# 1_PFC.net
KiCad netlist of a schematic drawn in Altium Designer
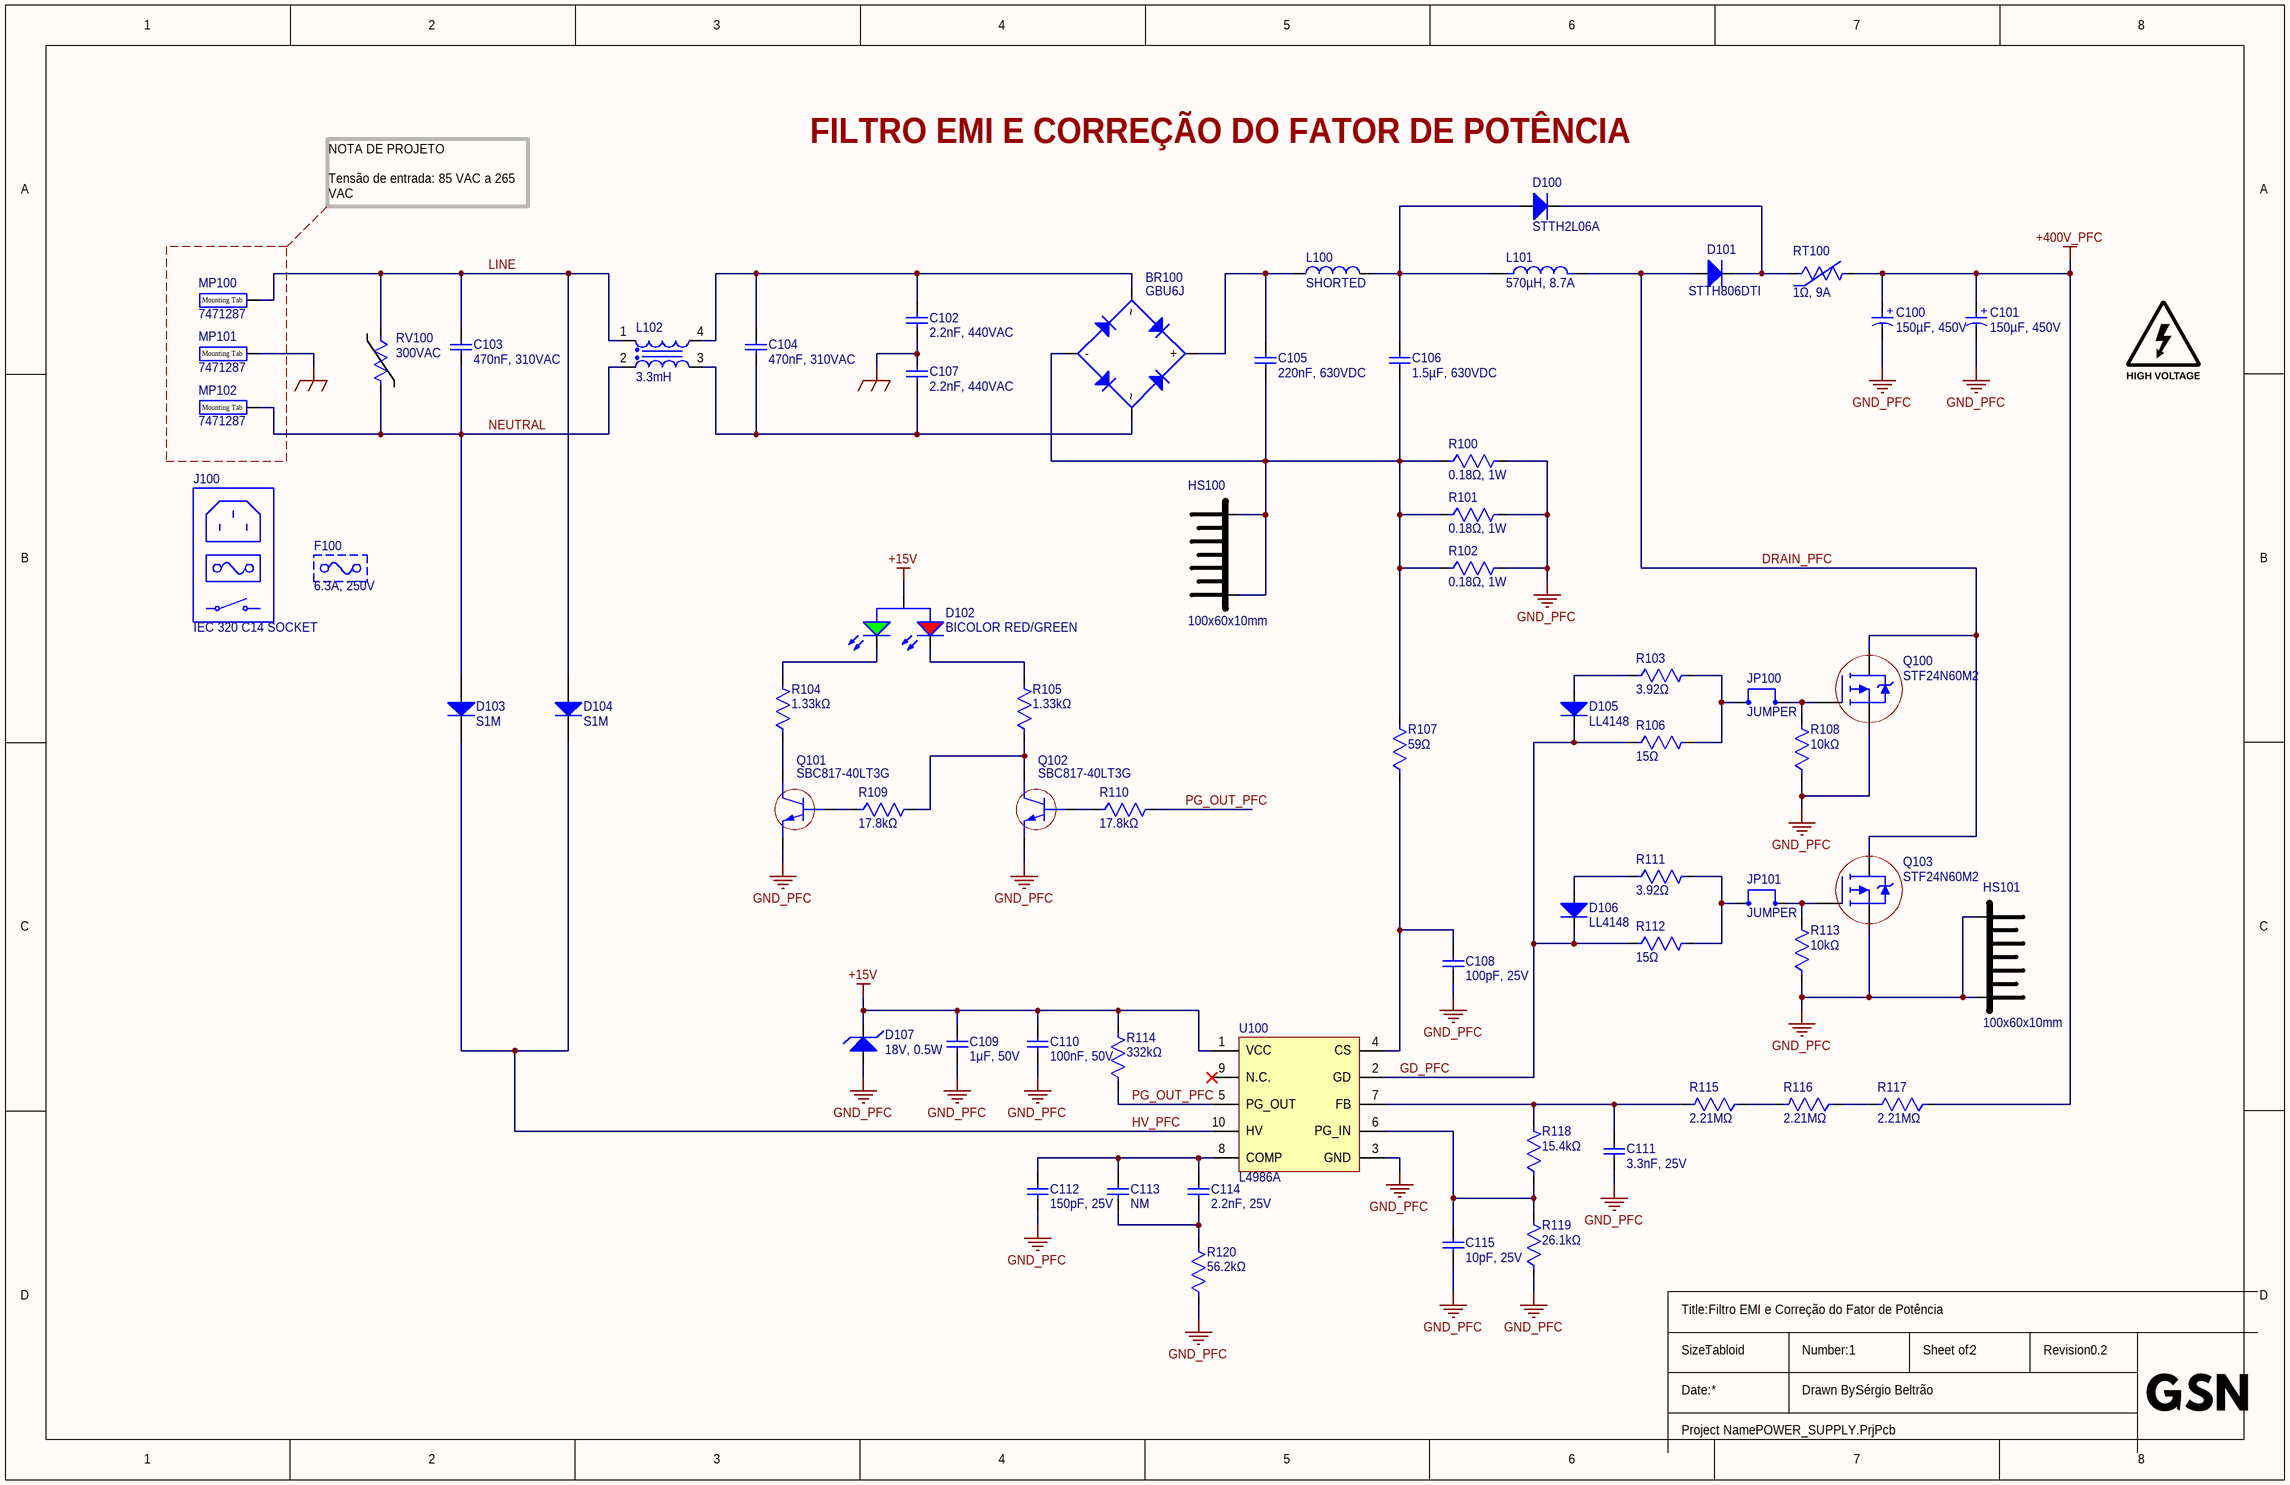
[diagram p0: 1_PFC.SchDoc]

(export (version "E")
  (design (tool "Eeschema 10.0.6"))
  (components
    (comp (ref "BR100")
      (value "GBU6J")
      (footprint "GBU")
      (description "BRIDGE RECT 1PHASE 600V 6A GBU")
      (fields (field (name "MANUFACTURER") "onsemi"))
      (libsource (lib "Bridge-Rectifiers") (part "GBU6J"))
    )
    (comp (ref "C100")
      (value "150µF, 450V")
      (footprint "WCAP-AIG8_D22H50")
      (description "WCAP-AIG8 Aluminum Electrolytic Capacitor, Snap-In, D22 x H50mm, 150µF, 450V")
      (fields
        (field (name "MANUFACTURER PART NUMBER") "861011483006")
        (field (name "MANUFACTURER") "Wurth Elektronik")
      )
      (libsource (lib "WE - Passive Components") (part "Capacitor_Polarized"))
    )
    (comp (ref "C101")
      (value "150µF, 450V")
      (footprint "WCAP-AIG8_D22H50")
      (description "WCAP-AIG8 Aluminum Electrolytic Capacitor, Snap-In, D22 x H50mm, 150µF, 450V")
      (fields
        (field (name "MANUFACTURER PART NUMBER") "861011483006")
        (field (name "MANUFACTURER") "Wurth Elektronik")
      )
      (libsource (lib "WE - Passive Components") (part "Capacitor_Polarized"))
    )
    (comp (ref "C102")
      (value "2.2nF, 440VAC")
      (footprint "CAP_5US63V7_VIS")
      (description "CAP CER 2200PF 440VAC Y5U RADIAL")
      (fields
        (field (name "MANUFACTURER") "Vishay")
        (field (name "MANUFACTURER PART NUMBER") "VY2222M35Y5US63V7")
      )
      (libsource (lib "Capacitors-PTH-Ceramic") (part "VY2222M35Y5US63V7"))
    )
    (comp (ref "C103")
      (value "470nF, 310VAC")
      (footprint "WCAP-FTXX_L18W8H14")
      (description "WCAP-FTXX Film Capacitor, THT, 18mm x 8mm x 14mm, 470nF, 310V")
      (fields
        (field (name "MANUFACTURER PART NUMBER") "890334025039CS")
        (field (name "MANUFACTURER") "Wurth Elektronik")
      )
      (libsource (lib "WE - Passive Components") (part "Capacitor_Non-Polarized"))
    )
    (comp (ref "C104")
      (value "470nF, 310VAC")
      (footprint "WCAP-FTXX_L18W8H14")
      (description "WCAP-FTXX Film Capacitor, THT, 18mm x 8mm x 14mm, 470nF, 310V")
      (fields
        (field (name "MANUFACTURER PART NUMBER") "890334025039CS")
        (field (name "MANUFACTURER") "Wurth Elektronik")
      )
      (libsource (lib "WE - Passive Components") (part "Capacitor_Non-Polarized"))
    )
    (comp (ref "C105")
      (value "220nF, 630VDC")
      (footprint "WCAP-FTXH_L18W8.5H14.5")
      (description "WCAP-FTXH THB X2-Capacitor, THT, L18 x W8.5 x H14.5mm, 220nF, 310V")
      (fields
        (field (name "MANUFACTURER PART NUMBER") "890414025003CS")
        (field (name "MANUFACTURER") "Wurth Elektronik")
      )
      (libsource (lib "WE - Passive Components") (part "Capacitor_Non-Polarized"))
    )
    (comp (ref "C106")
      (value "1.5µF, 630VDC")
      (footprint "WCAP-FTXH_L26.5W14.5H24.5")
      (description "WCAP-FTXH THB X2-Capacitor, THT, L26.5 x W14.5 x H24.5mm, 1.5µF, 310V")
      (fields
        (field (name "MANUFACTURER PART NUMBER") "890414026009CS")
        (field (name "MANUFACTURER") "Wurth Elektronik")
      )
      (libsource (lib "WE - Passive Components") (part "Capacitor_Non-Polarized"))
    )
    (comp (ref "C107")
      (value "2.2nF, 440VAC")
      (footprint "CAP_5US63V7_VIS")
      (description "CAP CER 2200PF 440VAC Y5U RADIAL")
      (fields
        (field (name "MANUFACTURER") "Vishay")
        (field (name "MANUFACTURER PART NUMBER") "VY2222M35Y5US63V7")
      )
      (libsource (lib "Capacitors-PTH-Ceramic") (part "VY2222M35Y5US63V7"))
    )
    (comp (ref "C108")
      (value "100pF, 25V")
      (footprint "WCAP-CSGP_0603_L1.6W0.8H0.8_Wave")
      (description "WCAP-CSGP Multilayer Ceramic Chip Capacitor, General Purpose, size 0603, 100pF, 25V")
      (fields
        (field (name "MANUFACTURER PART NUMBER") "885012206053")
        (field (name "MANUFACTURER") "Wurth Elektronik")
      )
      (libsource (lib "WE - Passive Components") (part "Capacitor_Non-Polarized"))
    )
    (comp (ref "C109")
      (value "1μF, 50V")
      (footprint "WCAP-CSGP_0603_L1.6W0.8H0.8_Wave")
      (description "WCAP-CSGP Multilayer Ceramic Chip Capacitor, General Purpose, size 0603, 1μF, 50V")
      (fields
        (field (name "MANUFACTURER PART NUMBER") "885012206126")
        (field (name "MANUFACTURER") "Wurth Elektronik")
      )
      (libsource (lib "WE - Passive Components") (part "Capacitor_Non-Polarized"))
    )
    (comp (ref "C110")
      (value "100nF, 50V")
      (footprint "WCAP-CSGP_0603_L1.6W0.8H0.8_Wave")
      (description "WCAP-CSGP Multilayer Ceramic Chip Capacitor, General Purpose, size 0603, 100nF, 50V")
      (fields
        (field (name "MANUFACTURER PART NUMBER") "885012206095R")
        (field (name "MANUFACTURER") "Wurth Elektronik")
      )
      (libsource (lib "WE - Passive Components") (part "Capacitor_Non-Polarized"))
    )
    (comp (ref "C111")
      (value "3.3nF, 25V")
      (footprint "WCAP-CSGP_0603_L1.6W0.8H0.8_Wave")
      (description "WCAP-CSGP Multilayer Ceramic Chip Capacitor, General Purpose, size 0603, 3.3nF, 25V")
      (fields
        (field (name "MANUFACTURER PART NUMBER") "885012206062")
        (field (name "MANUFACTURER") "Wurth Elektronik")
      )
      (libsource (lib "WE - Passive Components") (part "Capacitor_Non-Polarized"))
    )
    (comp (ref "C112")
      (value "150pF, 25V")
      (footprint "WCAP-CSGP_0603_L1.6W0.8H0.8_Wave")
      (description "WCAP-CSGP Multilayer Ceramic Chip Capacitor, General Purpose, size 0603, 150pF, 25V")
      (fields
        (field (name "MANUFACTURER PART NUMBER") "885012006039")
        (field (name "MANUFACTURER") "Wurth Elektronik")
      )
      (libsource (lib "WE - Passive Components") (part "Capacitor_Non-Polarized"))
    )
    (comp (ref "C113")
      (value "NM")
      (footprint "WCAP-CSGP_0603_L1.6W0.8H0.8_Wave")
      (description "WCAP-CSGP Multilayer Ceramic Chip Capacitor, General Purpose, size 0603, 470nF, 25V")
      (fields
        (field (name "MANUFACTURER PART NUMBER") "885012106020")
        (field (name "MANUFACTURER") "Wurth Elektronik")
      )
      (libsource (lib "WE - Passive Components") (part "Capacitor_Non-Polarized"))
    )
    (comp (ref "C114")
      (value "2.2nF, 25V")
      (footprint "WCAP-CSGP_0603_L1.6W0.8H0.8_Wave")
      (description "WCAP-CSGP Multilayer Ceramic Chip Capacitor, General Purpose, size 0603, 2.2nF, 25V")
      (fields
        (field (name "MANUFACTURER PART NUMBER") "885012206061")
        (field (name "MANUFACTURER") "Wurth Elektronik")
      )
      (libsource (lib "WE - Passive Components") (part "Capacitor_Non-Polarized"))
    )
    (comp (ref "C115")
      (value "10pF, 25V")
      (footprint "WCAP-CSGP_0603_L1.6W0.8H0.8_Wave")
      (description "WCAP-CSGP Multilayer Ceramic Chip Capacitor, General Purpose, size 0603, 10pF, 25V")
      (fields
        (field (name "MANUFACTURER PART NUMBER") "885012006032")
        (field (name "MANUFACTURER") "Wurth Elektronik")
      )
      (libsource (lib "WE - Passive Components") (part "Capacitor_Non-Polarized"))
    )
    (comp (ref "D100")
      (value "STTH2L06A")
      (footprint "SMA")
      (description "DIODE STANDARD 600V 2A SMA")
      (fields (field (name "MANUFACTURER") "STMicroelectronics"))
      (libsource (lib "Diodes") (part "STTH2L06A"))
    )
    (comp (ref "D101")
      (value "STTH806DTI")
      (footprint "TO-220AC")
      (description "DIODE STD 600V 8A TO220AC INS")
      (fields (field (name "MANUFACTURER") "STMicroelectronics"))
      (libsource (lib "Diodes") (part "STTH806DTI"))
    )
    (comp (ref "D102")
      (value "BICOLOR RED/GREEN")
      (footprint "LED_3MM_GREEN_RED")
      (description "LED GREEN/RED DIFF T-3MM TRI T/H")
      (fields
        (field (name "MANUFACTURER") "Lumex")
        (field (name "MANUFACTURER PART NUMBER") "SSL-LX3059IGW-CA")
      )
      (libsource (lib "LEDs") (part "SSL-LX3059IGW-CA"))
    )
    (comp (ref "D103")
      (value "S1M")
      (footprint "SMA")
      (description "DIODE STANDARD 1000V 1A DO214AC")
      (fields (field (name "MANUFACTURER") "onsemi") (field (name "VOLTAGE") "1kV"))
      (libsource (lib "Diodes") (part "S1M"))
    )
    (comp (ref "D104")
      (value "S1M")
      (footprint "SMA")
      (description "DIODE STANDARD 1000V 1A DO214AC")
      (fields (field (name "MANUFACTURER") "onsemi") (field (name "VOLTAGE") "1kV"))
      (libsource (lib "Diodes") (part "S1M"))
    )
    (comp (ref "D105")
      (value "LL4148")
      (footprint "SOD-80-DIODE")
      (description "DIODE STANDARD 100V 200MA SOD80")
      (fields (field (name "MANUFACTURER") "onsemi") (field (name "VOLTAGE") "100V"))
      (libsource (lib "Diodes") (part "LL4148"))
    )
    (comp (ref "D106")
      (value "LL4148")
      (footprint "SOD-80-DIODE")
      (description "DIODE STANDARD 100V 200MA SOD80")
      (fields (field (name "MANUFACTURER") "onsemi") (field (name "VOLTAGE") "100V"))
      (libsource (lib "Diodes") (part "LL4148"))
    )
    (comp (ref "D107")
      (value "18V, 0.5W")
      (footprint "SOD-80-DIODE")
      (description "DIODE ZENER 18V 500MW SOD80C")
      (fields (field (name "MANUFACTURER") "Diotec") (field (name "MANUFACTURER PART NUMBER") "ZMM18B"))
      (libsource (lib "Diodes") (part "ZMM18B"))
    )
    (comp (ref "F100")
      (value "6.3A, 250V")
      (description "FUSE GLASS 6.3A 250VAC 5X20MM")
      (fields
        (field (name "MANUFACTURER") "Bel Fuse")
        (field (name "MANUFACTURER PART NUMBER") "0652C6300-11")
      )
      (libsource (lib "Fuses") (part "0652C6300-11"))
    )
    (comp (ref "GRPH100")
      (value "DANGER HIGH VOLTAGE ICON")
      (footprint "DANGER_HIGH_VOLTAGE")
      (description "GRAPHIC ICON")
      (libsource (lib "Icons") (part "DANGER HIGH VOLTAGE ICON"))
    )
    (comp (ref "HS100")
      (value "100x60x10mm")
      (footprint "HEATSINK_100MM_60MM_10MM")
      (description "GENERIC HEATSINK 100X60X10MM")
      (fields (field (name "MANUFACTURER") "OEM") (field (name "MANUFACTURER PART NUMBER") "None"))
      (libsource (lib "Electro-Mechanical") (part "GENERIC-HEATSINK-100X60X10MM"))
    )
    (comp (ref "HS101")
      (value "100x60x10mm")
      (footprint "HEATSINK_100MM_60MM_10MM")
      (description "GENERIC HEATSINK 100X60X10MM")
      (fields (field (name "MANUFACTURER") "OEM") (field (name "MANUFACTURER PART NUMBER") "None"))
      (libsource (lib "Electro-Mechanical") (part "GENERIC-HEATSINK-100X60X10MM"))
    )
    (comp (ref "J100")
      (value "IEC 320 C14 SOCKET")
      (fields (field (name "MANUFACTURER PART NUMBER") "AC-01B-1") (field (name "MANUFACTURER") "OEM"))
      (libsource (lib "Connectors") (part "AC-01B-1"))
    )
    (comp (ref "JP100")
      (value "JUMPER")
      (footprint "JUMPER_TX_8P2MM")
      (description "JUMPER SMD TX 8.2X1.5MM WHITE")
      (fields (field (name "MANUFACTURER") "OEM") (field (name "MANUFACTURER PART NUMBER") "None"))
      (libsource (lib "Connectors") (part "JUMPER-TX-8P2X1P5MM-WHITE"))
    )
    (comp (ref "JP101")
      (value "JUMPER")
      (footprint "JUMPER_TX_8P2MM")
      (description "JUMPER SMD TX 8.2X1.5MM WHITE")
      (fields (field (name "MANUFACTURER") "OEM") (field (name "MANUFACTURER PART NUMBER") "None"))
      (libsource (lib "Connectors") (part "JUMPER-TX-8P2X1P5MM-WHITE"))
    )
    (comp (ref "L100")
      (value "SHORTED")
      (footprint "7447070")
      (description "WE-FI THT Leaded Toroidal Line Choke, 100uH, 6A, 0.035Ohm")
      (fields
        (field (name "MANUFACTURER PART NUMBER") "7447070")
        (field (name "MANUFACTURER") "Wurth Elektronik")
      )
      (libsource (lib "WE - Passive Components") (part "Inductor - 1"))
    )
    (comp (ref "L101")
      (value "570µH, 8.7A")
      (footprint "IND-TOR-MMTR014901_NO_MH")
      (description "FIXED IND 570UH 8.7A 65MOHM KOOL MU CORE")
      (fields (field (name "MANUFACTURER PART NUMBER") "MMTR014901") (field (name "MANUFACTURER") "Legrand"))
      (libsource (lib "Fixed-Inductors") (part "MMTR014901"))
    )
    (comp (ref "L102")
      (value "3.3mH")
      (footprint "WE-CMB_Type XL_L30W21H35")
      (description "WE-CMB Common Mode Power Line Choke, THT, Type XL, 3.3mH, 6A, 25mΩ")
      (fields
        (field (name "MANUFACTURER PART NUMBER") "7448256033")
        (field (name "MANUFACTURER") "Wurth Elektronik")
      )
      (libsource (lib "WE - Passive Components") (part "WE-CMB"))
    )
    (comp (ref "MP100")
      (value "7471287")
      (footprint "7471287")
      (description "WA-MTAB Mounting Tab, THT, Vertical, Male, Blade 6.35mm")
      (fields (field (name "MANUFACTURER") "Wurth Elektronik"))
      (libsource (lib "WE - Electromechanical Components") (part "Mounting Tab"))
    )
    (comp (ref "MP101")
      (value "7471287")
      (footprint "7471287")
      (description "WA-MTAB Mounting Tab, THT, Vertical, Male, Blade 6.35mm")
      (fields (field (name "MANUFACTURER") "Wurth Elektronik"))
      (libsource (lib "WE - Electromechanical Components") (part "Mounting Tab"))
    )
    (comp (ref "MP102")
      (value "7471287")
      (footprint "7471287")
      (description "WA-MTAB Mounting Tab, THT, Vertical, Male, Blade 6.35mm")
      (fields (field (name "MANUFACTURER") "Wurth Elektronik"))
      (libsource (lib "WE - Electromechanical Components") (part "Mounting Tab"))
    )
    (comp (ref "Q100")
      (value "STF24N60M2")
      (footprint "TO-220FP")
      (description "MOSFET N-CH 600V 18A TO220FP")
      (fields (field (name "MANUFACTURER") "STMicroelectronics"))
      (libsource (lib "Transistors") (part "STF24N60M2"))
    )
    (comp (ref "Q101")
      (value "SBC817-40LT3G")
      (footprint "SOT-23-3")
      (description "TRANS NPN 45V 0.5A SOT23-3")
      (fields (field (name "MANUFACTURER") "onsemi"))
      (libsource (lib "Transistors") (part "SBC817-40LT3G"))
    )
    (comp (ref "Q102")
      (value "SBC817-40LT3G")
      (footprint "SOT-23-3")
      (description "TRANS NPN 45V 0.5A SOT23-3")
      (fields (field (name "MANUFACTURER") "onsemi"))
      (libsource (lib "Transistors") (part "SBC817-40LT3G"))
    )
    (comp (ref "Q103")
      (value "STF24N60M2")
      (footprint "TO-220FP")
      (description "MOSFET N-CH 600V 18A TO220FP")
      (fields (field (name "MANUFACTURER") "STMicroelectronics"))
      (libsource (lib "Transistors") (part "STF24N60M2"))
    )
    (comp (ref "R100")
      (value "0.18Ω, 1W")
      (footprint "2512-WAVE")
      (description "RES 0.18 OHM 1% 1W 2512")
      (fields
        (field (name "MANUFACTURER") "Yageo Group")
        (field (name "MANUFACTURER PART NUMBER") "RL2512FK-070R18L")
      )
      (libsource (lib "Resistors-2512-Shunt") (part "RL2512FK-070R18L"))
    )
    (comp (ref "R101")
      (value "0.18Ω, 1W")
      (footprint "2512-WAVE")
      (description "RES 0.18 OHM 1% 1W 2512")
      (fields
        (field (name "MANUFACTURER") "Yageo Group")
        (field (name "MANUFACTURER PART NUMBER") "RL2512FK-070R18L")
      )
      (libsource (lib "Resistors-2512-Shunt") (part "RL2512FK-070R18L"))
    )
    (comp (ref "R102")
      (value "0.18Ω, 1W")
      (footprint "2512-WAVE")
      (description "RES 0.18 OHM 1% 1W 2512")
      (fields
        (field (name "MANUFACTURER") "Yageo Group")
        (field (name "MANUFACTURER PART NUMBER") "RL2512FK-070R18L")
      )
      (libsource (lib "Resistors-2512-Shunt") (part "RL2512FK-070R18L"))
    )
    (comp (ref "R103")
      (value "3.92Ω")
      (footprint "0805-WAVE")
      (description "RES 3.92 OHM 1% 1/8W 0805")
      (fields
        (field (name "MANUFACTURER") "Yageo Group")
        (field (name "MANUFACTURER PART NUMBER") "RC0805FR-073R92L")
      )
      (libsource (lib "Resistors-0805-E96-Yageo") (part "RC0805FR-073R92L"))
    )
    (comp (ref "R104")
      (value "1.33kΩ")
      (footprint "1206-WAVE")
      (description "RES 1.33K OHM 1% 1/4W 1206")
      (fields
        (field (name "MANUFACTURER") "Yageo Group")
        (field (name "MANUFACTURER PART NUMBER") "RC1206FR-071K33L")
      )
      (libsource (lib "Resistors-1206-E96-Yageo") (part "RC1206FR-071K33L"))
    )
    (comp (ref "R105")
      (value "1.33kΩ")
      (footprint "1206-WAVE")
      (description "RES 1.33K OHM 1% 1/4W 1206")
      (fields
        (field (name "MANUFACTURER") "Yageo Group")
        (field (name "MANUFACTURER PART NUMBER") "RC1206FR-071K33L")
      )
      (libsource (lib "Resistors-1206-E96-Yageo") (part "RC1206FR-071K33L"))
    )
    (comp (ref "R106")
      (value "15Ω")
      (footprint "0805-WAVE")
      (description "RES 15 OHM 1% 1/8W 0805")
      (fields
        (field (name "MANUFACTURER") "Yageo Group")
        (field (name "MANUFACTURER PART NUMBER") "RC0805FR-0715RL")
      )
      (libsource (lib "Resistors-0805-E96-Yageo") (part "RC0805FR-0715RL"))
    )
    (comp (ref "R107")
      (value "59Ω")
      (footprint "1206-WAVE")
      (description "RES 59 OHM 1% 1/4W 1206")
      (fields
        (field (name "MANUFACTURER") "Yageo Group")
        (field (name "MANUFACTURER PART NUMBER") "RC1206FR-0759RL")
      )
      (libsource (lib "Resistors-1206-E96-Yageo") (part "RC1206FR-0759RL"))
    )
    (comp (ref "R108")
      (value "10kΩ")
      (footprint "0805-WAVE")
      (description "RES 10K OHM 1% 1/8W 0805")
      (fields
        (field (name "MANUFACTURER") "Yageo Group")
        (field (name "MANUFACTURER PART NUMBER") "RC0805FR-0710KL")
      )
      (libsource (lib "Resistors-0805-E96-Yageo") (part "RC0805FR-0710KL"))
    )
    (comp (ref "R109")
      (value "17.8kΩ")
      (footprint "0603-WAVE")
      (description "RES 17.8K OHM 1% 1/10W 0603")
      (fields
        (field (name "MANUFACTURER PART NUMBER") "RC0603FR-0717K8L")
        (field (name "MANUFACTURER") "Yageo Group")
      )
      (libsource (lib "Resistors-0603-E96-Yageo") (part "RC0603FR-0717K8L"))
    )
    (comp (ref "R110")
      (value "17.8kΩ")
      (footprint "0603-WAVE")
      (description "RES 17.8K OHM 1% 1/10W 0603")
      (fields
        (field (name "MANUFACTURER PART NUMBER") "RC0603FR-0717K8L")
        (field (name "MANUFACTURER") "Yageo Group")
      )
      (libsource (lib "Resistors-0603-E96-Yageo") (part "RC0603FR-0717K8L"))
    )
    (comp (ref "R111")
      (value "3.92Ω")
      (footprint "0805-WAVE")
      (description "RES 3.92 OHM 1% 1/8W 0805")
      (fields
        (field (name "MANUFACTURER") "Yageo Group")
        (field (name "MANUFACTURER PART NUMBER") "RC0805FR-073R92L")
      )
      (libsource (lib "Resistors-0805-E96-Yageo") (part "RC0805FR-073R92L"))
    )
    (comp (ref "R112")
      (value "15Ω")
      (footprint "0805-WAVE")
      (description "RES 15 OHM 1% 1/8W 0805")
      (fields
        (field (name "MANUFACTURER") "Yageo Group")
        (field (name "MANUFACTURER PART NUMBER") "RC0805FR-0715RL")
      )
      (libsource (lib "Resistors-0805-E96-Yageo") (part "RC0805FR-0715RL"))
    )
    (comp (ref "R113")
      (value "10kΩ")
      (footprint "0805-WAVE")
      (description "RES 10K OHM 1% 1/8W 0805")
      (fields
        (field (name "MANUFACTURER") "Yageo Group")
        (field (name "MANUFACTURER PART NUMBER") "RC0805FR-0710KL")
      )
      (libsource (lib "Resistors-0805-E96-Yageo") (part "RC0805FR-0710KL"))
    )
    (comp (ref "R114")
      (value "332kΩ")
      (footprint "0603-WAVE")
      (description "RES 332K OHM 1% 1/10W 0603")
      (fields
        (field (name "MANUFACTURER PART NUMBER") "RC0603FR-07332KL")
        (field (name "MANUFACTURER") "Yageo Group")
      )
      (libsource (lib "Resistors-0603-E96-Yageo") (part "RC0603FR-07332KL"))
    )
    (comp (ref "R115")
      (value "2.21MΩ")
      (footprint "1206-WAVE")
      (description "RES 2.21M OHM 1% 1/4W 1206")
      (fields
        (field (name "MANUFACTURER") "Yageo Group")
        (field (name "MANUFACTURER PART NUMBER") "RC1206FR-072M21L")
      )
      (libsource (lib "Resistors-1206-E96-Yageo") (part "RC1206FR-072M21L"))
    )
    (comp (ref "R116")
      (value "2.21MΩ")
      (footprint "1206-WAVE")
      (description "RES 2.21M OHM 1% 1/4W 1206")
      (fields
        (field (name "MANUFACTURER") "Yageo Group")
        (field (name "MANUFACTURER PART NUMBER") "RC1206FR-072M21L")
      )
      (libsource (lib "Resistors-1206-E96-Yageo") (part "RC1206FR-072M21L"))
    )
    (comp (ref "R117")
      (value "2.21MΩ")
      (footprint "1206-WAVE")
      (description "RES 2.21M OHM 1% 1/4W 1206")
      (fields
        (field (name "MANUFACTURER") "Yageo Group")
        (field (name "MANUFACTURER PART NUMBER") "RC1206FR-072M21L")
      )
      (libsource (lib "Resistors-1206-E96-Yageo") (part "RC1206FR-072M21L"))
    )
    (comp (ref "R118")
      (value "15.4kΩ")
      (footprint "0603-WAVE")
      (description "RES 15.4K OHM 1% 1/10W 0603")
      (fields
        (field (name "MANUFACTURER PART NUMBER") "RC0603FR-0715K4L")
        (field (name "MANUFACTURER") "Yageo Group")
      )
      (libsource (lib "Resistors-0603-E96-Yageo") (part "RC0603FR-0715K4L"))
    )
    (comp (ref "R119")
      (value "26.1kΩ")
      (footprint "0603-WAVE")
      (description "RES 26.1K OHM 1% 1/10W 0603")
      (fields
        (field (name "MANUFACTURER PART NUMBER") "RC0603FR-0726K1L")
        (field (name "MANUFACTURER") "Yageo Group")
      )
      (libsource (lib "Resistors-0603-E96-Yageo") (part "RC0603FR-0726K1L"))
    )
    (comp (ref "R120")
      (value "56.2kΩ")
      (footprint "0603-WAVE")
      (description "RES 56.2K OHM 1% 1/10W 0603")
      (fields
        (field (name "MANUFACTURER PART NUMBER") "RC0603FR-0756K2L")
        (field (name "MANUFACTURER") "Yageo Group")
      )
      (libsource (lib "Resistors-0603-E96-Yageo") (part "RC0603FR-0756K2L"))
    )
    (comp (ref "RT100")
      (value "1Ω, 9A")
      (footprint "B57237S0109M054")
      (description "NTC THERMISTOR ICL S237/1/M54")
      (fields
        (field (name "MANUFACTURER") "EPCOS")
        (field (name "MANUFACTURER PART NUMBER") "B57237S0109M054")
      )
      (libsource (lib "NTCs") (part "B57237S0109M054"))
    )
    (comp (ref "RV100")
      (value "300VAC")
      (footprint "MOV-B72214S0301K101")
      (description "Var MOV 300VAC/385VDC 4500A 470V Thru-Hole Radial Automotive Bulk")
      (fields
        (field (name "MANUFACTURER") "EPCOS")
        (field (name "MANUFACTURER PART NUMBER") "B72214S0301K101")
      )
      (libsource (lib "Varistors") (part "B72214S0301K101"))
    )
    (comp (ref "U100")
      (value "L4986A")
      (footprint "SSOP-10")
      (description "CCM PFC CONTROLLER WITH HIGH VOL")
      (fields (field (name "MANUFACTURER") "STMicroelectronics"))
      (libsource (lib "Power-Management-ICs") (part "L4986A"))
    )
  )
  (nets
    (net (code "1") (name "+15V") (class "Default")
      (node (ref "C109") (pin "2") (pinfunction "2_2") (pintype "passive"))
      (node (ref "C110") (pin "2") (pinfunction "2_2") (pintype "passive"))
      (node (ref "D102") (pin "2") (pinfunction "A_2") (pintype "passive"))
      (node (ref "D107") (pin "1") (pinfunction "K_1") (pintype "passive"))
      (node (ref "R114") (pin "2") (pinfunction "2_2") (pintype "passive"))
      (node (ref "U100") (pin "1") (pinfunction "VCC_1") (pintype "passive"))
    )
    (net (code "2") (name "+400V_PFC") (class "Default")
      (node (ref "C100") (pin "1") (pinfunction "P_1") (pintype "passive"))
      (node (ref "C101") (pin "1") (pinfunction "P_1") (pintype "passive"))
      (node (ref "R117") (pin "1") (pinfunction "1_1") (pintype "passive"))
      (node (ref "RT100") (pin "2") (pinfunction "2_2") (pintype "passive"))
    )
    (net (code "3") (name "/DRAIN_PFC") (class "Default")
      (node (ref "D101") (pin "2") (pinfunction "A_2") (pintype "passive"))
      (node (ref "L101") (pin "2") (pinfunction "2_2") (pintype "passive"))
      (node (ref "Q100") (pin "2") (pinfunction "DRAIN_2") (pintype "passive"))
      (node (ref "Q103") (pin "2") (pinfunction "DRAIN_2") (pintype "passive"))
    )
    (net (code "4") (name "/GD_PFC") (class "Default")
      (node (ref "D105") (pin "1") (pinfunction "K_1") (pintype "passive"))
      (node (ref "D106") (pin "1") (pinfunction "K_1") (pintype "passive"))
      (node (ref "R106") (pin "1") (pinfunction "1_1") (pintype "passive"))
      (node (ref "R112") (pin "1") (pinfunction "1_1") (pintype "passive"))
      (node (ref "U100") (pin "2") (pinfunction "GD_2") (pintype "passive"))
    )
    (net (code "5") (name "/HV_PFC") (class "Default")
      (node (ref "D103") (pin "1") (pinfunction "K_1") (pintype "passive"))
      (node (ref "D104") (pin "1") (pinfunction "K_1") (pintype "passive"))
      (node (ref "U100") (pin "10") (pinfunction "HV_10") (pintype "passive"))
    )
    (net (code "6") (name "/LINE") (class "Default")
      (node (ref "C103") (pin "2") (pinfunction "2_2") (pintype "passive"))
      (node (ref "D104") (pin "2") (pinfunction "A_2") (pintype "passive"))
      (node (ref "L102") (pin "1") (pinfunction "1_1") (pintype "passive"))
      (node (ref "MP100") (pin "1") (pinfunction "1_1") (pintype "passive"))
      (node (ref "RV100") (pin "1") (pinfunction "1_1") (pintype "passive"))
    )
    (net (code "7") (name "/NEUTRAL") (class "Default")
      (node (ref "C103") (pin "1") (pinfunction "1_1") (pintype "passive"))
      (node (ref "D103") (pin "2") (pinfunction "A_2") (pintype "passive"))
      (node (ref "L102") (pin "2") (pinfunction "2_2") (pintype "passive"))
      (node (ref "MP102") (pin "1") (pinfunction "1_1") (pintype "passive"))
      (node (ref "RV100") (pin "2") (pinfunction "2_2") (pintype "passive"))
    )
    (net (code "8") (name "/PG_OUT_PFC") (class "Default")
      (node (ref "R110") (pin "2") (pinfunction "2_2") (pintype "passive"))
      (node (ref "R114") (pin "1") (pinfunction "1_1") (pintype "passive"))
      (node (ref "U100") (pin "5") (pinfunction "PG_OUT_5") (pintype "passive"))
    )
    (net (code "9") (name "EARTH") (class "Default")
      (node (ref "C102") (pin "1") (pinfunction "1_1") (pintype "passive"))
      (node (ref "C107") (pin "2") (pinfunction "2_2") (pintype "passive"))
      (node (ref "MP101") (pin "1") (pinfunction "1_1") (pintype "passive"))
    )
    (net (code "10") (name "GND_PFC") (class "Default")
      (node (ref "C100") (pin "2") (pinfunction "N_2") (pintype "passive"))
      (node (ref "C101") (pin "2") (pinfunction "N_2") (pintype "passive"))
      (node (ref "C108") (pin "1") (pinfunction "1_1") (pintype "passive"))
      (node (ref "C109") (pin "1") (pinfunction "1_1") (pintype "passive"))
      (node (ref "C110") (pin "1") (pinfunction "1_1") (pintype "passive"))
      (node (ref "C111") (pin "1") (pinfunction "1_1") (pintype "passive"))
      (node (ref "C112") (pin "1") (pinfunction "1_1") (pintype "passive"))
      (node (ref "C115") (pin "1") (pinfunction "1_1") (pintype "passive"))
      (node (ref "D107") (pin "2") (pinfunction "A_2") (pintype "passive"))
      (node (ref "HS101") (pin "H1") (pinfunction "H1_H1") (pintype "passive"))
      (node (ref "HS101") (pin "H2") (pinfunction "H2_H2") (pintype "passive"))
      (node (ref "Q100") (pin "3") (pinfunction "SOURCE_3") (pintype "passive"))
      (node (ref "Q101") (pin "2") (pinfunction "E_2") (pintype "passive"))
      (node (ref "Q102") (pin "2") (pinfunction "E_2") (pintype "passive"))
      (node (ref "Q103") (pin "3") (pinfunction "SOURCE_3") (pintype "passive"))
      (node (ref "R100") (pin "2") (pinfunction "2_2") (pintype "passive"))
      (node (ref "R101") (pin "2") (pinfunction "2_2") (pintype "passive"))
      (node (ref "R102") (pin "2") (pinfunction "2_2") (pintype "passive"))
      (node (ref "R108") (pin "1") (pinfunction "1_1") (pintype "passive"))
      (node (ref "R113") (pin "1") (pinfunction "1_1") (pintype "passive"))
      (node (ref "R119") (pin "1") (pinfunction "1_1") (pintype "passive"))
      (node (ref "R120") (pin "1") (pinfunction "1_1") (pintype "passive"))
      (node (ref "U100") (pin "3") (pinfunction "GND_3") (pintype "passive"))
    )
    (net (code "11") (name "Net-(BR100-+)") (class "Default")
      (node (ref "BR100") (pin "1") (pinfunction "+_1") (pintype "passive"))
      (node (ref "C105") (pin "2") (pinfunction "2_2") (pintype "passive"))
      (node (ref "L100") (pin "1") (pinfunction "1_1") (pintype "passive"))
    )
    (net (code "12") (name "Net-(BR100--)") (class "Default")
      (node (ref "BR100") (pin "4") (pinfunction "-_4") (pintype "passive"))
      (node (ref "C105") (pin "1") (pinfunction "1_1") (pintype "passive"))
      (node (ref "C106") (pin "1") (pinfunction "1_1") (pintype "passive"))
      (node (ref "HS100") (pin "H1") (pinfunction "H1_H1") (pintype "passive"))
      (node (ref "HS100") (pin "H2") (pinfunction "H2_H2") (pintype "passive"))
      (node (ref "R100") (pin "1") (pinfunction "1_1") (pintype "passive"))
      (node (ref "R101") (pin "1") (pinfunction "1_1") (pintype "passive"))
      (node (ref "R102") (pin "1") (pinfunction "1_1") (pintype "passive"))
      (node (ref "R107") (pin "2") (pinfunction "2_2") (pintype "passive"))
    )
    (net (code "13") (name "Net-(BR100-~-Pad2)") (class "Default")
      (node (ref "BR100") (pin "2") (pinfunction "~_2") (pintype "passive"))
      (node (ref "C102") (pin "2") (pinfunction "2_2") (pintype "passive"))
      (node (ref "C104") (pin "2") (pinfunction "2_2") (pintype "passive"))
      (node (ref "L102") (pin "4") (pinfunction "4_4") (pintype "passive"))
    )
    (net (code "14") (name "Net-(BR100-~-Pad3)") (class "Default")
      (node (ref "BR100") (pin "3") (pinfunction "~_3") (pintype "passive"))
      (node (ref "C104") (pin "1") (pinfunction "1_1") (pintype "passive"))
      (node (ref "C107") (pin "1") (pinfunction "1_1") (pintype "passive"))
      (node (ref "L102") (pin "3") (pinfunction "3_3") (pintype "passive"))
    )
    (net (code "15") (name "Net-(C113-Pad1)") (class "Default")
      (node (ref "C113") (pin "1") (pinfunction "1_1") (pintype "passive"))
      (node (ref "C114") (pin "1") (pinfunction "1_1") (pintype "passive"))
      (node (ref "R120") (pin "2") (pinfunction "2_2") (pintype "passive"))
    )
    (net (code "16") (name "Net-(D100-A)") (class "Default")
      (node (ref "C106") (pin "2") (pinfunction "2_2") (pintype "passive"))
      (node (ref "D100") (pin "2") (pinfunction "A_2") (pintype "passive"))
      (node (ref "L100") (pin "2") (pinfunction "2_2") (pintype "passive"))
      (node (ref "L101") (pin "1") (pinfunction "1_1") (pintype "passive"))
    )
    (net (code "17") (name "Net-(D100-K)") (class "Default")
      (node (ref "D100") (pin "1") (pinfunction "K_1") (pintype "passive"))
      (node (ref "D101") (pin "1") (pinfunction "K_1") (pintype "passive"))
      (node (ref "RT100") (pin "1") (pinfunction "1_1") (pintype "passive"))
    )
    (net (code "18") (name "Net-(D102-KG)") (class "Default")
      (node (ref "D102") (pin "1") (pinfunction "KG_1") (pintype "passive"))
      (node (ref "R104") (pin "2") (pinfunction "2_2") (pintype "passive"))
    )
    (net (code "19") (name "Net-(D102-KR)") (class "Default")
      (node (ref "D102") (pin "3") (pinfunction "KR_3") (pintype "passive"))
      (node (ref "R105") (pin "2") (pinfunction "2_2") (pintype "passive"))
    )
    (net (code "20") (name "Net-(D105-A)") (class "Default")
      (node (ref "D105") (pin "2") (pinfunction "A_2") (pintype "passive"))
      (node (ref "R103") (pin "1") (pinfunction "1_1") (pintype "passive"))
    )
    (net (code "21") (name "Net-(D106-A)") (class "Default")
      (node (ref "D106") (pin "2") (pinfunction "A_2") (pintype "passive"))
      (node (ref "R111") (pin "1") (pinfunction "1_1") (pintype "passive"))
    )
    (net (code "22") (name "Net-(JP100-Pad1)") (class "Default")
      (node (ref "JP100") (pin "1") (pinfunction "1_1") (pintype "passive"))
      (node (ref "R103") (pin "2") (pinfunction "2_2") (pintype "passive"))
      (node (ref "R106") (pin "2") (pinfunction "2_2") (pintype "passive"))
    )
    (net (code "23") (name "Net-(JP101-Pad1)") (class "Default")
      (node (ref "JP101") (pin "1") (pinfunction "1_1") (pintype "passive"))
      (node (ref "R111") (pin "2") (pinfunction "2_2") (pintype "passive"))
      (node (ref "R112") (pin "2") (pinfunction "2_2") (pintype "passive"))
    )
    (net (code "24") (name "Net-(Q100-GATE)") (class "Default")
      (node (ref "JP100") (pin "2") (pinfunction "2_2") (pintype "passive"))
      (node (ref "Q100") (pin "1") (pinfunction "GATE_1") (pintype "passive"))
      (node (ref "R108") (pin "2") (pinfunction "2_2") (pintype "passive"))
    )
    (net (code "25") (name "Net-(Q101-B)") (class "Default")
      (node (ref "Q101") (pin "1") (pinfunction "B_1") (pintype "passive"))
      (node (ref "R109") (pin "1") (pinfunction "1_1") (pintype "passive"))
    )
    (net (code "26") (name "Net-(Q101-C)") (class "Default")
      (node (ref "Q101") (pin "3") (pinfunction "C_3") (pintype "passive"))
      (node (ref "R104") (pin "1") (pinfunction "1_1") (pintype "passive"))
    )
    (net (code "27") (name "Net-(Q102-B)") (class "Default")
      (node (ref "Q102") (pin "1") (pinfunction "B_1") (pintype "passive"))
      (node (ref "R110") (pin "1") (pinfunction "1_1") (pintype "passive"))
    )
    (net (code "28") (name "Net-(Q102-C)") (class "Default")
      (node (ref "Q102") (pin "3") (pinfunction "C_3") (pintype "passive"))
      (node (ref "R105") (pin "1") (pinfunction "1_1") (pintype "passive"))
      (node (ref "R109") (pin "2") (pinfunction "2_2") (pintype "passive"))
    )
    (net (code "29") (name "Net-(Q103-GATE)") (class "Default")
      (node (ref "JP101") (pin "2") (pinfunction "2_2") (pintype "passive"))
      (node (ref "Q103") (pin "1") (pinfunction "GATE_1") (pintype "passive"))
      (node (ref "R113") (pin "2") (pinfunction "2_2") (pintype "passive"))
    )
    (net (code "30") (name "Net-(R115-Pad1)") (class "Default")
      (node (ref "R115") (pin "1") (pinfunction "1_1") (pintype "passive"))
      (node (ref "R116") (pin "2") (pinfunction "2_2") (pintype "passive"))
    )
    (net (code "31") (name "Net-(R116-Pad1)") (class "Default")
      (node (ref "R116") (pin "1") (pinfunction "1_1") (pintype "passive"))
      (node (ref "R117") (pin "2") (pinfunction "2_2") (pintype "passive"))
    )
    (net (code "32") (name "Net-(U100-COMP)") (class "Default")
      (node (ref "C112") (pin "2") (pinfunction "2_2") (pintype "passive"))
      (node (ref "C113") (pin "2") (pinfunction "2_2") (pintype "passive"))
      (node (ref "C114") (pin "2") (pinfunction "2_2") (pintype "passive"))
      (node (ref "U100") (pin "8") (pinfunction "COMP_8") (pintype "passive"))
    )
    (net (code "33") (name "Net-(U100-CS)") (class "Default")
      (node (ref "C108") (pin "2") (pinfunction "2_2") (pintype "passive"))
      (node (ref "R107") (pin "1") (pinfunction "1_1") (pintype "passive"))
      (node (ref "U100") (pin "4") (pinfunction "CS_4") (pintype "passive"))
    )
    (net (code "34") (name "Net-(U100-FB)") (class "Default")
      (node (ref "C111") (pin "2") (pinfunction "2_2") (pintype "passive"))
      (node (ref "R115") (pin "2") (pinfunction "2_2") (pintype "passive"))
      (node (ref "R118") (pin "2") (pinfunction "2_2") (pintype "passive"))
      (node (ref "U100") (pin "7") (pinfunction "FB_7") (pintype "passive"))
    )
    (net (code "35") (name "Net-(U100-PG_IN)") (class "Default")
      (node (ref "C115") (pin "2") (pinfunction "2_2") (pintype "passive"))
      (node (ref "R118") (pin "1") (pinfunction "1_1") (pintype "passive"))
      (node (ref "R119") (pin "2") (pinfunction "2_2") (pintype "passive"))
      (node (ref "U100") (pin "6") (pinfunction "PG_IN_6") (pintype "passive"))
    )
    (net (code "36") (name "unconnected-(U100-N.C.-Pad9)") (class "Default")
      (node (ref "U100") (pin "9") (pinfunction "N.C._9") (pintype "passive+no_connect"))
    )
  )
)
